# FEEL_2021_power_management.net
KiCad netlist of a schematic drawn in Altium Designer
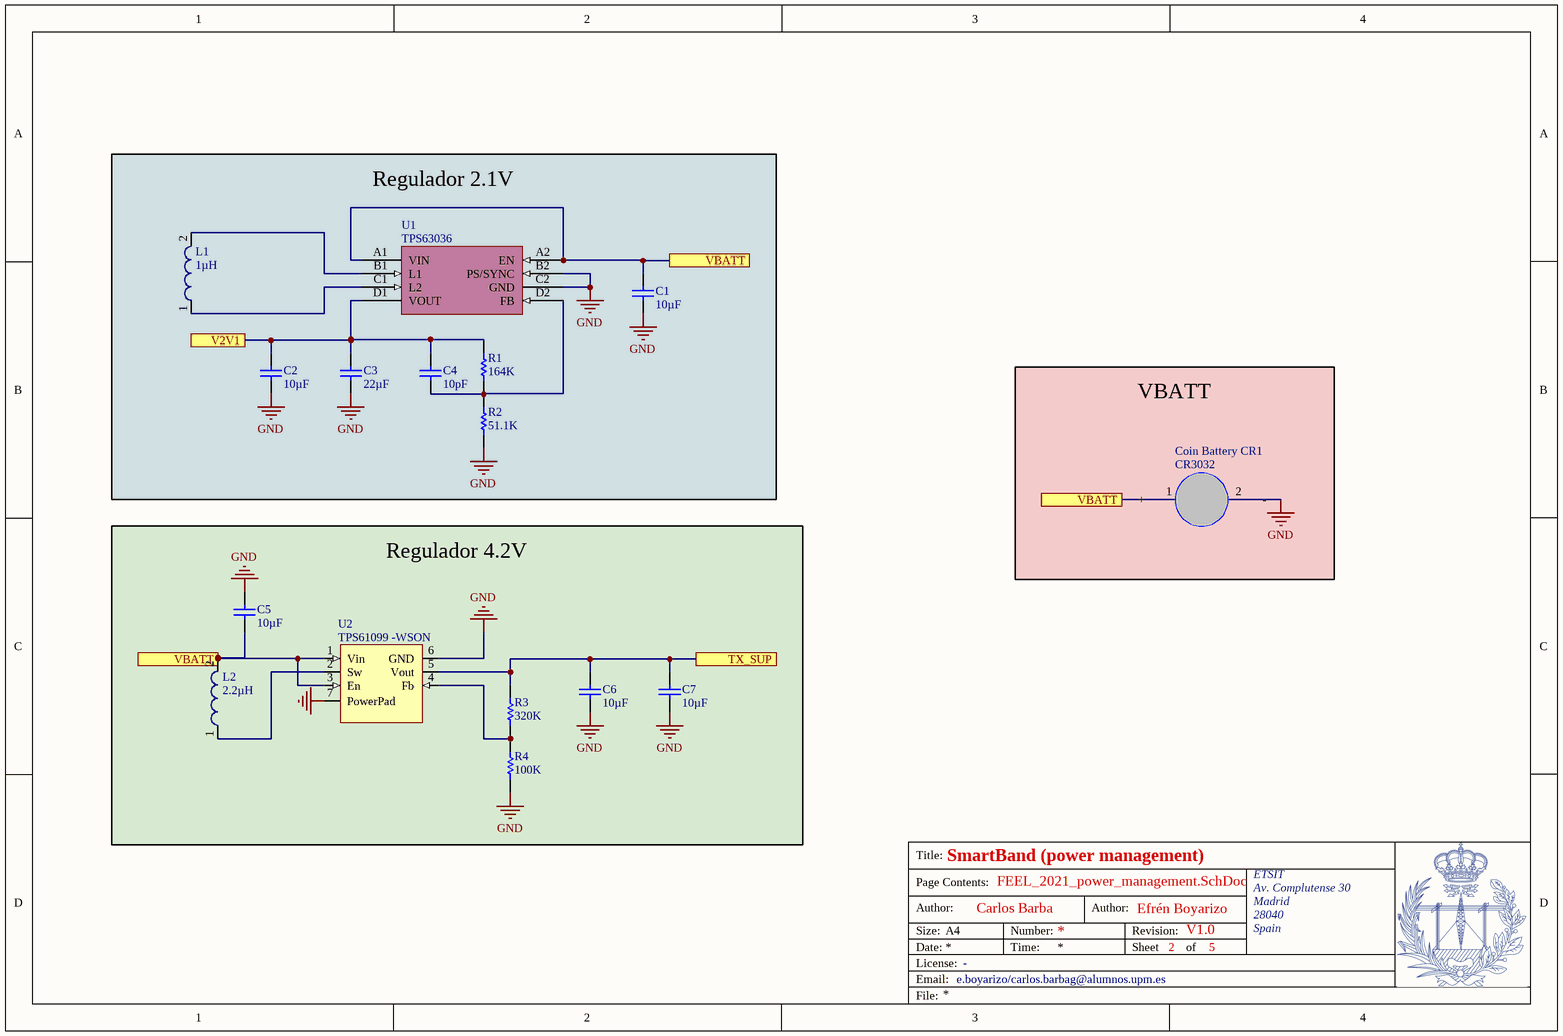
[diagram p0: FEEL_2021_power_management.SchDoc]

(export (version "E")
  (design (tool "Eeschema 10.0.6"))
  (components
    (comp (ref "C1")
      (value "10µF")
      (footprint "CAPC1608X90X35ML10T15")
      (fields (field (name "MANUFACTURER") "Murata"))
      (libsource (lib "Altium Content Vault") (part "CAP-NP-2"))
    )
    (comp (ref "C2")
      (value "10µF")
      (footprint "CAPC1608X90X35ML10T15")
      (fields (field (name "MANUFACTURER") "Murata"))
      (libsource (lib "Altium Content Vault") (part "CAP-NP-2"))
    )
    (comp (ref "C3")
      (value "22µF")
      (footprint "CAPC1608X90X35ML10T15")
      (fields (field (name "MANUFACTURER") "Murata"))
      (libsource (lib "Altium Content Vault") (part "CAP-NP-2"))
    )
    (comp (ref "C4")
      (value "10pF")
      (footprint "CAPC1608X90X35ML10T15")
      (fields (field (name "MANUFACTURER") "Murata"))
      (libsource (lib "Altium Content Vault") (part "CAP-NP-2"))
    )
    (comp (ref "C5")
      (value "10µF")
      (footprint "CAPC1608X90X35ML10T15")
      (fields (field (name "MANUFACTURER") "Murata"))
      (libsource (lib "Altium Content Vault") (part "CAP-NP-2"))
    )
    (comp (ref "C6")
      (value "10µF")
      (footprint "CAPC1608X90X35ML10T15")
      (fields (field (name "MANUFACTURER") "Murata"))
      (libsource (lib "Altium Content Vault") (part "CAP-NP-2"))
    )
    (comp (ref "C7")
      (value "10µF")
      (footprint "CAPC1608X90X35ML10T15")
      (fields (field (name "MANUFACTURER") "Murata"))
      (libsource (lib "Altium Content Vault") (part "CAP-NP-2"))
    )
    (comp (ref "Coin Battery CR1")
      (value "~")
      (footprint "CR3032")
      (libsource (lib "FEEL2122") (part "CR3032"))
    )
    (comp (ref "L1")
      (value "1µH")
      (footprint "SMD 2510")
      (description "Power Multilayer Inductor WE-MAPI, L=10.0µH")
      (fields (field (name "PARTNUMBER") "74438323100") (field (name "MANUFACTURER") "Wuerth Elektronik"))
      (libsource (lib "Altium Content Vault") (part "WE-IND-INDUCTOR-2"))
    )
    (comp (ref "L2")
      (value "2.2µH")
      (footprint "SMD 2510")
      (description "Power Multilayer Inductor WE-MAPI, L=10.0µH")
      (fields (field (name "PARTNUMBER") "74438323100") (field (name "MANUFACTURER") "Wuerth Elektronik"))
      (libsource (lib "Altium Content Vault") (part "WE-IND-INDUCTOR-2"))
    )
    (comp (ref "R1")
      (value "164K")
      (footprint "RESC1609X50X30NL8T20")
      (description "Chip Resistor, 0 Ohm, Jumper, 100 mW, -55 to 155 degC, 0603 (1608 Metric), RoHS, Tape and Reel")
      (fields (field (name "MANUFACTURER") "Vishay Semiconductor"))
      (libsource (lib "Altium Content Vault") (part "RES-2"))
    )
    (comp (ref "R2")
      (value "51.1K")
      (footprint "RESC1609X50X30NL8T20")
      (description "Chip Resistor, 0 Ohm, Jumper, 100 mW, -55 to 155 degC, 0603 (1608 Metric), RoHS, Tape and Reel")
      (fields (field (name "MANUFACTURER") "Vishay Semiconductor"))
      (libsource (lib "Altium Content Vault") (part "RES-2"))
    )
    (comp (ref "R3")
      (value "320K")
      (footprint "RESC1609X50X30NL8T20")
      (description "Chip Resistor, 0 Ohm, Jumper, 100 mW, -55 to 155 degC, 0603 (1608 Metric), RoHS, Tape and Reel")
      (fields (field (name "MANUFACTURER") "Vishay Semiconductor"))
      (libsource (lib "Altium Content Vault") (part "RES-2"))
    )
    (comp (ref "R4")
      (value "100K")
      (footprint "RESC1609X50X30NL8T20")
      (description "Chip Resistor, 0 Ohm, Jumper, 100 mW, -55 to 155 degC, 0603 (1608 Metric), RoHS, Tape and Reel")
      (fields (field (name "MANUFACTURER") "Vishay Semiconductor"))
      (libsource (lib "Altium Content Vault") (part "RES-2"))
    )
    (comp (ref "U1") (value "~") (footprint "tps63036") (libsource (lib "FEEL2122") (part "TPS63036")))
    (comp (ref "U2") (value "~") (footprint "SOP6") (libsource (lib "FEEL2122") (part "TSP61099-WSON")))
  )
  (nets
    (net (code "1") (name "/TX_SUP") (class "Default")
      (node (ref "C6") (pin "2") (pinfunction "2_2") (pintype "passive"))
      (node (ref "C7") (pin "2") (pinfunction "2_2") (pintype "passive"))
      (node (ref "R3") (pin "1") (pinfunction "1_1") (pintype "passive"))
      (node (ref "U2") (pin "5") (pinfunction "Vout_5") (pintype "power_in"))
    )
    (net (code "2") (name "/V2V1") (class "Default")
      (node (ref "C2") (pin "2") (pinfunction "2_2") (pintype "passive"))
      (node (ref "C3") (pin "2") (pinfunction "2_2") (pintype "passive"))
      (node (ref "C4") (pin "2") (pinfunction "2_2") (pintype "passive"))
      (node (ref "R1") (pin "2") (pinfunction "2_2") (pintype "passive"))
      (node (ref "U1") (pin "D1") (pinfunction "VOUT_D1") (pintype "power_in"))
    )
    (net (code "3") (name "/VBATT") (class "Default")
      (node (ref "C1") (pin "2") (pinfunction "2_2") (pintype "passive"))
      (node (ref "C5") (pin "1") (pinfunction "1_1") (pintype "passive"))
      (node (ref "Coin Battery CR1") (pin "1") (pinfunction "+_1") (pintype "passive"))
      (node (ref "L2") (pin "2") (pinfunction "2_2") (pintype "passive"))
      (node (ref "U1") (pin "A1") (pinfunction "VIN_A1") (pintype "power_in"))
      (node (ref "U1") (pin "A2") (pinfunction "EN_A2") (pintype "input"))
      (node (ref "U2") (pin "1") (pinfunction "Vin_1") (pintype "input"))
      (node (ref "U2") (pin "3") (pinfunction "En_3") (pintype "input"))
    )
    (net (code "4") (name "GND") (class "Default")
      (node (ref "C1") (pin "1") (pinfunction "1_1") (pintype "passive"))
      (node (ref "C2") (pin "1") (pinfunction "1_1") (pintype "passive"))
      (node (ref "C3") (pin "1") (pinfunction "1_1") (pintype "passive"))
      (node (ref "C5") (pin "2") (pinfunction "2_2") (pintype "passive"))
      (node (ref "C6") (pin "1") (pinfunction "1_1") (pintype "passive"))
      (node (ref "C7") (pin "1") (pinfunction "1_1") (pintype "passive"))
      (node (ref "Coin Battery CR1") (pin "2") (pinfunction "-_2") (pintype "passive"))
      (node (ref "R2") (pin "2") (pinfunction "2_2") (pintype "passive"))
      (node (ref "R4") (pin "2") (pinfunction "2_2") (pintype "passive"))
      (node (ref "U1") (pin "B2") (pinfunction "PS/SYNC_B2") (pintype "input"))
      (node (ref "U1") (pin "C2") (pinfunction "GND_C2") (pintype "power_in"))
      (node (ref "U2") (pin "6") (pinfunction "GND_6") (pintype "power_in"))
      (node (ref "U2") (pin "7") (pinfunction "PowerPad_7") (pintype "power_in"))
    )
    (net (code "5") (name "Net-(U1-FB)") (class "Default")
      (node (ref "C4") (pin "1") (pinfunction "1_1") (pintype "passive"))
      (node (ref "R1") (pin "1") (pinfunction "1_1") (pintype "passive"))
      (node (ref "R2") (pin "1") (pinfunction "1_1") (pintype "passive"))
      (node (ref "U1") (pin "D2") (pinfunction "FB_D2") (pintype "input"))
    )
    (net (code "6") (name "Net-(U1-L1)") (class "Default")
      (node (ref "L1") (pin "2") (pinfunction "2_2") (pintype "passive"))
      (node (ref "U1") (pin "B1") (pinfunction "L1_B1") (pintype "input"))
    )
    (net (code "7") (name "Net-(U1-L2)") (class "Default")
      (node (ref "L1") (pin "1") (pinfunction "1_1") (pintype "passive"))
      (node (ref "U1") (pin "C1") (pinfunction "L2_C1") (pintype "input"))
    )
    (net (code "8") (name "Net-(U2-Fb)") (class "Default")
      (node (ref "R3") (pin "2") (pinfunction "2_2") (pintype "passive"))
      (node (ref "R4") (pin "1") (pinfunction "1_1") (pintype "passive"))
      (node (ref "U2") (pin "4") (pinfunction "Fb_4") (pintype "input"))
    )
    (net (code "9") (name "Net-(U2-Sw)") (class "Default")
      (node (ref "L2") (pin "1") (pinfunction "1_1") (pintype "passive"))
      (node (ref "U2") (pin "2") (pinfunction "Sw_2") (pintype "power_in"))
    )
  )
)
